# CONNECTOR.net
KiCad netlist of a schematic drawn in Altium Designer
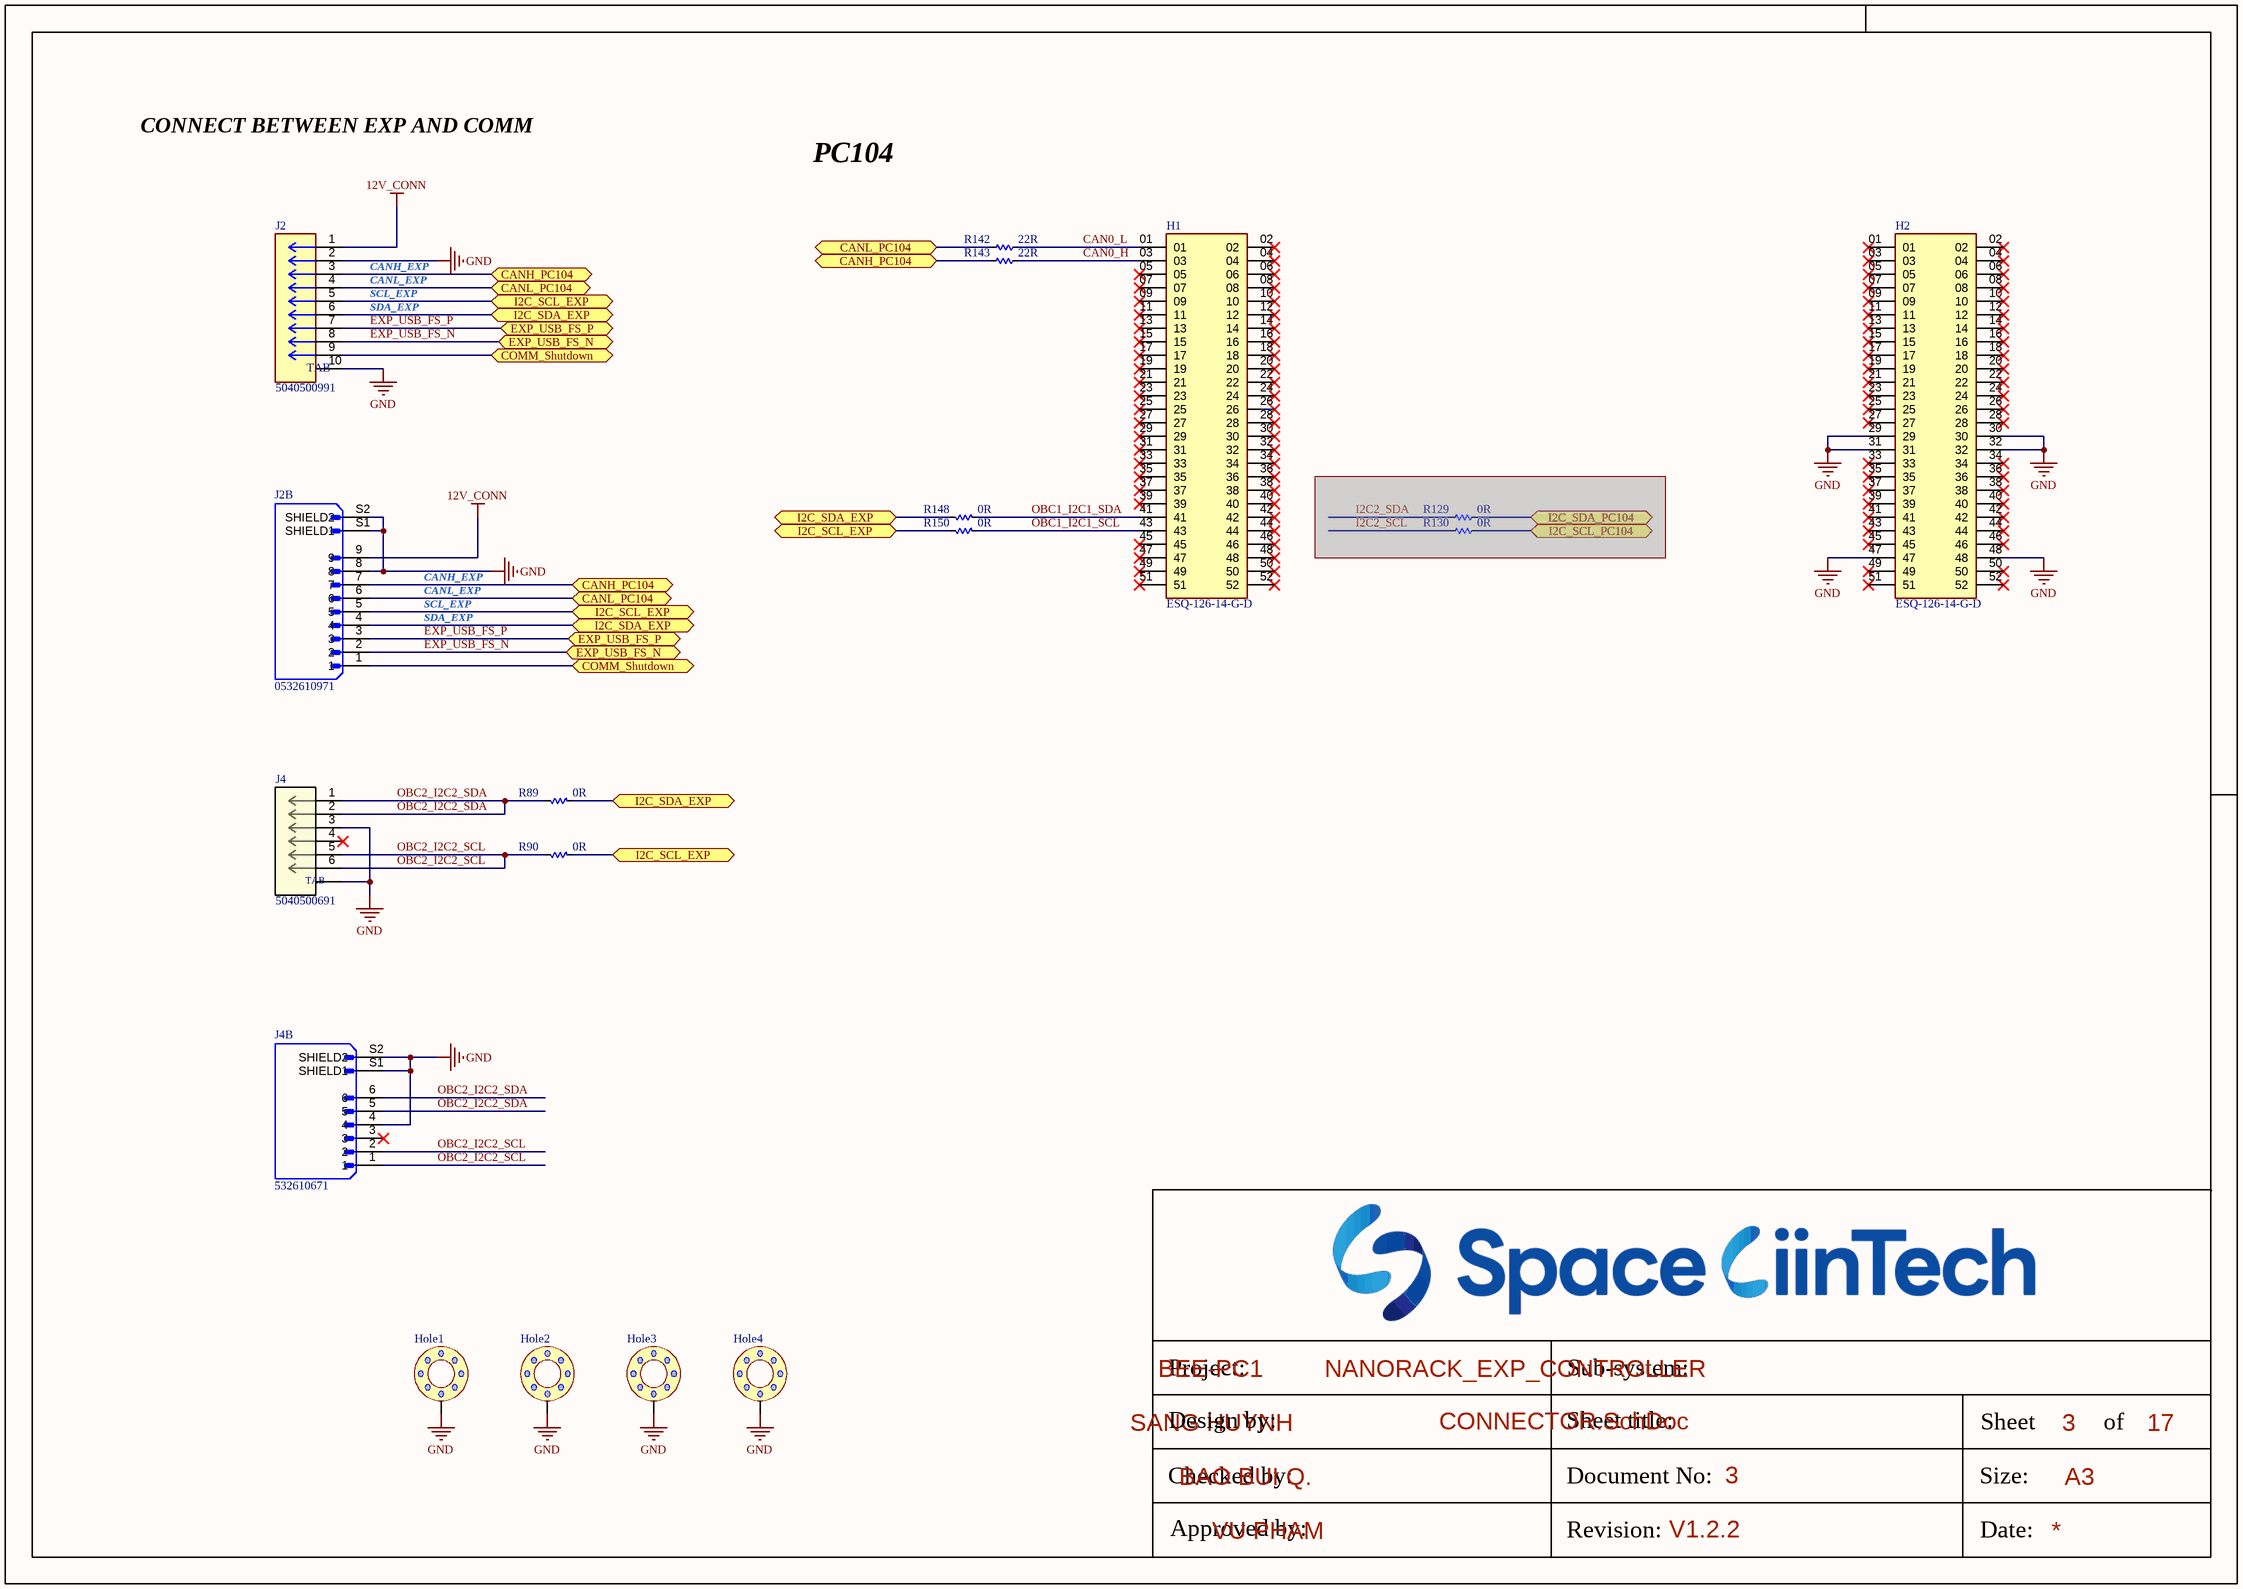
[diagram p0: CONNECTOR.SchDoc]

(export (version "E")
  (design (tool "Eeschema 10.0.6"))
  (components
    (comp (ref "H1")
      (value "ESQ-126-14-G-D")
      (footprint "SAMTEC_ESQ-126-14-G-D")
      (fields (field (name "MF") "Samtec"))
      (libsource (lib "COMM_SCHLIB") (part "ESQ-126-14-G-D"))
    )
    (comp (ref "H2")
      (value "ESQ-126-14-G-D")
      (footprint "SAMTEC_ESQ-126-14-G-D")
      (fields (field (name "MF") "Samtec"))
      (libsource (lib "COMM_SCHLIB") (part "ESQ-126-14-G-D"))
    )
    (comp (ref "Hole1")
      (value "hole_space")
      (footprint "HOLE_SPACE")
      (libsource (lib "COMM_SCHLIB") (part "hole_space"))
    )
    (comp (ref "Hole2")
      (value "hole_space")
      (footprint "HOLE_SPACE")
      (libsource (lib "COMM_SCHLIB") (part "hole_space"))
    )
    (comp (ref "Hole3")
      (value "hole_space")
      (footprint "HOLE_SPACE")
      (libsource (lib "COMM_SCHLIB") (part "hole_space"))
    )
    (comp (ref "Hole4")
      (value "hole_space")
      (footprint "HOLE_SPACE")
      (libsource (lib "COMM_SCHLIB") (part "hole_space"))
    )
    (comp (ref "J2")
      (value "5040500991")
      (footprint "5040500991")
      (description "Connector Header Surface Mount, Right Angle 9 position 0.059\" (1.50mm)")
      (libsource (lib "COMM_SCHLIB") (part "5040500991"))
    )
    (comp (ref "J2B")
      (value "0532610971")
      (footprint "0532610971")
      (description "CONN HEADER SMD R/A 9POS 1.25MM")
      (libsource (lib "COMM_SCHLIB") (part "CONN_SMD_09"))
    )
    (comp (ref "J4")
      (value "5040500691")
      (footprint "5040500691")
      (fields (field (name "COPYRIGHT") "Copyright (C) 2025 Ultra Librarian. All rights reserved."))
      (libsource (lib "COMM_SCHLIB") (part "5040500691"))
    )
    (comp (ref "J4B")
      (value "532610671")
      (footprint "MOLEX_532610671")
      (libsource (lib "COMM_SCHLIB") (part "CONN_SMD_06"))
    )
    (comp (ref "R89")
      (value "0R")
      (footprint "RES_C_1608X60")
      (description "RES")
      (libsource (lib "LABLIB") (part "_RES_B_2"))
    )
    (comp (ref "R90")
      (value "0R")
      (footprint "RES_C_1608X60")
      (description "RES")
      (libsource (lib "LABLIB") (part "_RES_B_2"))
    )
    (comp (ref "R129")
      (value "0R")
      (footprint "RES_C_1608X60")
      (description "RES")
      (libsource (lib "LABLIB") (part "_RES_B_2"))
    )
    (comp (ref "R130")
      (value "0R")
      (footprint "RES_C_1608X60")
      (description "RES")
      (libsource (lib "LABLIB") (part "_RES_B_2"))
    )
    (comp (ref "R142")
      (value "22R")
      (footprint "RES_C_1608X60")
      (description "RES")
      (libsource (lib "LABLIB") (part "_RES_B_2"))
    )
    (comp (ref "R143")
      (value "22R")
      (footprint "RES_C_1608X60")
      (description "RES")
      (libsource (lib "LABLIB") (part "_RES_B_2"))
    )
    (comp (ref "R148")
      (value "0R")
      (footprint "RES_C_1608X60")
      (description "RES")
      (libsource (lib "LABLIB") (part "_RES_B_2"))
    )
    (comp (ref "R150")
      (value "0R")
      (footprint "RES_C_1608X60")
      (description "RES")
      (libsource (lib "LABLIB") (part "_RES_B_2"))
    )
  )
  (nets
    (net (code "1") (name "/CAN0_H") (class "Default")
      (node (ref "H1") (pin "03") (pinfunction "03_03") (pintype "passive"))
      (node (ref "R143") (pin "2") (pinfunction "2_2") (pintype "passive"))
    )
    (net (code "2") (name "/CAN0_L") (class "Default")
      (node (ref "H1") (pin "01") (pinfunction "01_01") (pintype "passive"))
      (node (ref "R142") (pin "2") (pinfunction "2_2") (pintype "passive"))
    )
    (net (code "3") (name "/CANH_PC104") (class "Default")
      (node (ref "J2") (pin "3") (pinfunction "3_3") (pintype "passive"))
      (node (ref "J2B") (pin "7") (pinfunction "7_7") (pintype "passive"))
      (node (ref "R143") (pin "1") (pinfunction "1_1") (pintype "passive"))
    )
    (net (code "4") (name "/CANL_PC104") (class "Default")
      (node (ref "J2") (pin "4") (pinfunction "4_4") (pintype "passive"))
      (node (ref "J2B") (pin "6") (pinfunction "6_6") (pintype "passive"))
      (node (ref "R142") (pin "1") (pinfunction "1_1") (pintype "passive"))
    )
    (net (code "5") (name "/COMM_Shutdown") (class "Default")
      (node (ref "J2") (pin "9") (pinfunction "9_9") (pintype "passive"))
      (node (ref "J2B") (pin "1") (pinfunction "1_1") (pintype "passive"))
    )
    (net (code "6") (name "/EXP_USB_FS_N") (class "Default")
      (node (ref "J2") (pin "8") (pinfunction "8_8") (pintype "passive"))
      (node (ref "J2B") (pin "2") (pinfunction "2_2") (pintype "passive"))
    )
    (net (code "7") (name "/EXP_USB_FS_P") (class "Default")
      (node (ref "J2") (pin "7") (pinfunction "7_7") (pintype "passive"))
      (node (ref "J2B") (pin "3") (pinfunction "3_3") (pintype "passive"))
    )
    (net (code "8") (name "/I2C2_SCL") (class "Default")
      (node (ref "R130") (pin "1") (pinfunction "1_1") (pintype "passive"))
    )
    (net (code "9") (name "/I2C2_SDA") (class "Default")
      (node (ref "R129") (pin "1") (pinfunction "1_1") (pintype "passive"))
    )
    (net (code "10") (name "/I2C_SCL_EXP") (class "Default")
      (node (ref "J2") (pin "5") (pinfunction "5_5") (pintype "passive"))
      (node (ref "J2B") (pin "5") (pinfunction "5_5") (pintype "passive"))
      (node (ref "R150") (pin "2") (pinfunction "2_2") (pintype "passive"))
      (node (ref "R90") (pin "1") (pinfunction "1_1") (pintype "passive"))
    )
    (net (code "11") (name "/I2C_SCL_PC104") (class "Default")
      (node (ref "R130") (pin "2") (pinfunction "2_2") (pintype "passive"))
    )
    (net (code "12") (name "/I2C_SDA_EXP") (class "Default")
      (node (ref "J2") (pin "6") (pinfunction "6_6") (pintype "passive"))
      (node (ref "J2B") (pin "4") (pinfunction "4_4") (pintype "passive"))
      (node (ref "R148") (pin "2") (pinfunction "2_2") (pintype "passive"))
      (node (ref "R89") (pin "1") (pinfunction "1_1") (pintype "passive"))
    )
    (net (code "13") (name "/I2C_SDA_PC104") (class "Default")
      (node (ref "R129") (pin "2") (pinfunction "2_2") (pintype "passive"))
    )
    (net (code "14") (name "/OBC1_I2C1_SCL") (class "Default")
      (node (ref "H1") (pin "43") (pinfunction "43_43") (pintype "passive"))
      (node (ref "R150") (pin "1") (pinfunction "1_1") (pintype "passive"))
    )
    (net (code "15") (name "/OBC1_I2C1_SDA") (class "Default")
      (node (ref "H1") (pin "41") (pinfunction "41_41") (pintype "passive"))
      (node (ref "R148") (pin "1") (pinfunction "1_1") (pintype "passive"))
    )
    (net (code "16") (name "/OBC2_I2C2_SCL") (class "Default")
      (node (ref "J4") (pin "5") (pinfunction "5_5") (pintype "passive"))
      (node (ref "J4") (pin "6") (pinfunction "6_6") (pintype "passive"))
      (node (ref "J4B") (pin "1") (pinfunction "1_1") (pintype "passive"))
      (node (ref "J4B") (pin "2") (pinfunction "2_2") (pintype "passive"))
      (node (ref "R90") (pin "2") (pinfunction "2_2") (pintype "passive"))
    )
    (net (code "17") (name "/OBC2_I2C2_SDA") (class "Default")
      (node (ref "J4") (pin "1") (pinfunction "1_1") (pintype "passive"))
      (node (ref "J4") (pin "2") (pinfunction "2_2") (pintype "passive"))
      (node (ref "J4B") (pin "5") (pinfunction "5_5") (pintype "passive"))
      (node (ref "J4B") (pin "6") (pinfunction "6_6") (pintype "passive"))
      (node (ref "R89") (pin "2") (pinfunction "2_2") (pintype "passive"))
    )
    (net (code "18") (name "12V_CONN") (class "Default")
      (node (ref "J2") (pin "1") (pinfunction "1_1") (pintype "passive"))
      (node (ref "J2B") (pin "9") (pinfunction "9_9") (pintype "passive"))
    )
    (net (code "19") (name "GND") (class "Default")
      (node (ref "H2") (pin "29") (pinfunction "29_29") (pintype "passive"))
      (node (ref "H2") (pin "30") (pinfunction "30_30") (pintype "passive"))
      (node (ref "H2") (pin "31") (pinfunction "31_31") (pintype "passive"))
      (node (ref "H2") (pin "32") (pinfunction "32_32") (pintype "passive"))
      (node (ref "H2") (pin "47") (pinfunction "47_47") (pintype "passive"))
      (node (ref "H2") (pin "48") (pinfunction "48_48") (pintype "passive"))
      (node (ref "Hole1") (pin "1") (pinfunction "1_1") (pintype "passive"))
      (node (ref "Hole2") (pin "1") (pinfunction "1_1") (pintype "passive"))
      (node (ref "Hole3") (pin "1") (pinfunction "1_1") (pintype "passive"))
      (node (ref "Hole4") (pin "1") (pinfunction "1_1") (pintype "passive"))
      (node (ref "J2") (pin "10") (pinfunction "10_10") (pintype "passive"))
      (node (ref "J2") (pin "2") (pinfunction "2_2") (pintype "passive"))
      (node (ref "J2B") (pin "8") (pinfunction "8_8") (pintype "passive"))
      (node (ref "J2B") (pin "S1") (pinfunction "SHIELD1_S1") (pintype "passive"))
      (node (ref "J2B") (pin "S2") (pinfunction "SHIELD2_S2") (pintype "passive"))
      (node (ref "J4") (pin "3") (pinfunction "3_3") (pintype "passive"))
      (node (ref "J4") (pin "7") (pinfunction "7_7") (pintype "passive"))
      (node (ref "J4B") (pin "4") (pinfunction "4_4") (pintype "passive"))
      (node (ref "J4B") (pin "S1") (pinfunction "SHIELD1_S1") (pintype "passive"))
      (node (ref "J4B") (pin "S2") (pinfunction "SHIELD2_S2") (pintype "passive"))
    )
    (net (code "20") (name "unconnected-(H1-Pad02)") (class "Default")
      (node (ref "H1") (pin "02") (pinfunction "02_02") (pintype "passive+no_connect"))
    )
    (net (code "21") (name "unconnected-(H1-Pad04)") (class "Default")
      (node (ref "H1") (pin "04") (pinfunction "04_04") (pintype "passive+no_connect"))
    )
    (net (code "22") (name "unconnected-(H1-Pad05)") (class "Default")
      (node (ref "H1") (pin "05") (pinfunction "05_05") (pintype "passive+no_connect"))
    )
    (net (code "23") (name "unconnected-(H1-Pad06)") (class "Default")
      (node (ref "H1") (pin "06") (pinfunction "06_06") (pintype "passive+no_connect"))
    )
    (net (code "24") (name "unconnected-(H1-Pad07)") (class "Default")
      (node (ref "H1") (pin "07") (pinfunction "07_07") (pintype "passive+no_connect"))
    )
    (net (code "25") (name "unconnected-(H1-Pad08)") (class "Default")
      (node (ref "H1") (pin "08") (pinfunction "08_08") (pintype "passive+no_connect"))
    )
    (net (code "26") (name "unconnected-(H1-Pad09)") (class "Default")
      (node (ref "H1") (pin "09") (pinfunction "09_09") (pintype "passive+no_connect"))
    )
    (net (code "27") (name "unconnected-(H1-Pad10)") (class "Default")
      (node (ref "H1") (pin "10") (pinfunction "10_10") (pintype "passive+no_connect"))
    )
    (net (code "28") (name "unconnected-(H1-Pad11)") (class "Default")
      (node (ref "H1") (pin "11") (pinfunction "11_11") (pintype "passive+no_connect"))
    )
    (net (code "29") (name "unconnected-(H1-Pad12)") (class "Default")
      (node (ref "H1") (pin "12") (pinfunction "12_12") (pintype "passive+no_connect"))
    )
    (net (code "30") (name "unconnected-(H1-Pad13)") (class "Default")
      (node (ref "H1") (pin "13") (pinfunction "13_13") (pintype "passive+no_connect"))
    )
    (net (code "31") (name "unconnected-(H1-Pad14)") (class "Default")
      (node (ref "H1") (pin "14") (pinfunction "14_14") (pintype "passive+no_connect"))
    )
    (net (code "32") (name "unconnected-(H1-Pad15)") (class "Default")
      (node (ref "H1") (pin "15") (pinfunction "15_15") (pintype "passive+no_connect"))
    )
    (net (code "33") (name "unconnected-(H1-Pad16)") (class "Default")
      (node (ref "H1") (pin "16") (pinfunction "16_16") (pintype "passive+no_connect"))
    )
    (net (code "34") (name "unconnected-(H1-Pad17)") (class "Default")
      (node (ref "H1") (pin "17") (pinfunction "17_17") (pintype "passive+no_connect"))
    )
    (net (code "35") (name "unconnected-(H1-Pad18)") (class "Default")
      (node (ref "H1") (pin "18") (pinfunction "18_18") (pintype "passive+no_connect"))
    )
    (net (code "36") (name "unconnected-(H1-Pad19)") (class "Default")
      (node (ref "H1") (pin "19") (pinfunction "19_19") (pintype "passive+no_connect"))
    )
    (net (code "37") (name "unconnected-(H1-Pad20)") (class "Default")
      (node (ref "H1") (pin "20") (pinfunction "20_20") (pintype "passive+no_connect"))
    )
    (net (code "38") (name "unconnected-(H1-Pad21)") (class "Default")
      (node (ref "H1") (pin "21") (pinfunction "21_21") (pintype "passive+no_connect"))
    )
    (net (code "39") (name "unconnected-(H1-Pad22)") (class "Default")
      (node (ref "H1") (pin "22") (pinfunction "22_22") (pintype "passive+no_connect"))
    )
    (net (code "40") (name "unconnected-(H1-Pad23)") (class "Default")
      (node (ref "H1") (pin "23") (pinfunction "23_23") (pintype "passive+no_connect"))
    )
    (net (code "41") (name "unconnected-(H1-Pad24)") (class "Default")
      (node (ref "H1") (pin "24") (pinfunction "24_24") (pintype "passive+no_connect"))
    )
    (net (code "42") (name "unconnected-(H1-Pad25)") (class "Default")
      (node (ref "H1") (pin "25") (pinfunction "25_25") (pintype "passive+no_connect"))
    )
    (net (code "43") (name "unconnected-(H1-Pad26)") (class "Default")
      (node (ref "H1") (pin "26") (pinfunction "26_26") (pintype "passive+no_connect"))
    )
    (net (code "44") (name "unconnected-(H1-Pad27)") (class "Default")
      (node (ref "H1") (pin "27") (pinfunction "27_27") (pintype "passive+no_connect"))
    )
    (net (code "45") (name "unconnected-(H1-Pad28)") (class "Default")
      (node (ref "H1") (pin "28") (pinfunction "28_28") (pintype "passive+no_connect"))
    )
    (net (code "46") (name "unconnected-(H1-Pad29)") (class "Default")
      (node (ref "H1") (pin "29") (pinfunction "29_29") (pintype "passive+no_connect"))
    )
    (net (code "47") (name "unconnected-(H1-Pad30)") (class "Default")
      (node (ref "H1") (pin "30") (pinfunction "30_30") (pintype "passive+no_connect"))
    )
    (net (code "48") (name "unconnected-(H1-Pad31)") (class "Default")
      (node (ref "H1") (pin "31") (pinfunction "31_31") (pintype "passive+no_connect"))
    )
    (net (code "49") (name "unconnected-(H1-Pad32)") (class "Default")
      (node (ref "H1") (pin "32") (pinfunction "32_32") (pintype "passive+no_connect"))
    )
    (net (code "50") (name "unconnected-(H1-Pad33)") (class "Default")
      (node (ref "H1") (pin "33") (pinfunction "33_33") (pintype "passive+no_connect"))
    )
    (net (code "51") (name "unconnected-(H1-Pad34)") (class "Default")
      (node (ref "H1") (pin "34") (pinfunction "34_34") (pintype "passive+no_connect"))
    )
    (net (code "52") (name "unconnected-(H1-Pad35)") (class "Default")
      (node (ref "H1") (pin "35") (pinfunction "35_35") (pintype "passive+no_connect"))
    )
    (net (code "53") (name "unconnected-(H1-Pad36)") (class "Default")
      (node (ref "H1") (pin "36") (pinfunction "36_36") (pintype "passive+no_connect"))
    )
    (net (code "54") (name "unconnected-(H1-Pad37)") (class "Default")
      (node (ref "H1") (pin "37") (pinfunction "37_37") (pintype "passive+no_connect"))
    )
    (net (code "55") (name "unconnected-(H1-Pad38)") (class "Default")
      (node (ref "H1") (pin "38") (pinfunction "38_38") (pintype "passive+no_connect"))
    )
    (net (code "56") (name "unconnected-(H1-Pad39)") (class "Default")
      (node (ref "H1") (pin "39") (pinfunction "39_39") (pintype "passive+no_connect"))
    )
    (net (code "57") (name "unconnected-(H1-Pad40)") (class "Default")
      (node (ref "H1") (pin "40") (pinfunction "40_40") (pintype "passive+no_connect"))
    )
    (net (code "58") (name "unconnected-(H1-Pad42)") (class "Default")
      (node (ref "H1") (pin "42") (pinfunction "42_42") (pintype "passive+no_connect"))
    )
    (net (code "59") (name "unconnected-(H1-Pad44)") (class "Default")
      (node (ref "H1") (pin "44") (pinfunction "44_44") (pintype "passive+no_connect"))
    )
    (net (code "60") (name "unconnected-(H1-Pad45)") (class "Default")
      (node (ref "H1") (pin "45") (pinfunction "45_45") (pintype "passive+no_connect"))
    )
    (net (code "61") (name "unconnected-(H1-Pad46)") (class "Default")
      (node (ref "H1") (pin "46") (pinfunction "46_46") (pintype "passive+no_connect"))
    )
    (net (code "62") (name "unconnected-(H1-Pad47)") (class "Default")
      (node (ref "H1") (pin "47") (pinfunction "47_47") (pintype "passive+no_connect"))
    )
    (net (code "63") (name "unconnected-(H1-Pad48)") (class "Default")
      (node (ref "H1") (pin "48") (pinfunction "48_48") (pintype "passive+no_connect"))
    )
    (net (code "64") (name "unconnected-(H1-Pad49)") (class "Default")
      (node (ref "H1") (pin "49") (pinfunction "49_49") (pintype "passive+no_connect"))
    )
    (net (code "65") (name "unconnected-(H1-Pad50)") (class "Default")
      (node (ref "H1") (pin "50") (pinfunction "50_50") (pintype "passive+no_connect"))
    )
    (net (code "66") (name "unconnected-(H1-Pad51)") (class "Default")
      (node (ref "H1") (pin "51") (pinfunction "51_51") (pintype "passive+no_connect"))
    )
    (net (code "67") (name "unconnected-(H1-Pad52)") (class "Default")
      (node (ref "H1") (pin "52") (pinfunction "52_52") (pintype "passive+no_connect"))
    )
    (net (code "68") (name "unconnected-(H2-Pad01)") (class "Default")
      (node (ref "H2") (pin "01") (pinfunction "01_01") (pintype "passive+no_connect"))
    )
    (net (code "69") (name "unconnected-(H2-Pad02)") (class "Default")
      (node (ref "H2") (pin "02") (pinfunction "02_02") (pintype "passive+no_connect"))
    )
    (net (code "70") (name "unconnected-(H2-Pad03)") (class "Default")
      (node (ref "H2") (pin "03") (pinfunction "03_03") (pintype "passive+no_connect"))
    )
    (net (code "71") (name "unconnected-(H2-Pad04)") (class "Default")
      (node (ref "H2") (pin "04") (pinfunction "04_04") (pintype "passive+no_connect"))
    )
    (net (code "72") (name "unconnected-(H2-Pad05)") (class "Default")
      (node (ref "H2") (pin "05") (pinfunction "05_05") (pintype "passive+no_connect"))
    )
    (net (code "73") (name "unconnected-(H2-Pad06)") (class "Default")
      (node (ref "H2") (pin "06") (pinfunction "06_06") (pintype "passive+no_connect"))
    )
    (net (code "74") (name "unconnected-(H2-Pad07)") (class "Default")
      (node (ref "H2") (pin "07") (pinfunction "07_07") (pintype "passive+no_connect"))
    )
    (net (code "75") (name "unconnected-(H2-Pad08)") (class "Default")
      (node (ref "H2") (pin "08") (pinfunction "08_08") (pintype "passive+no_connect"))
    )
    (net (code "76") (name "unconnected-(H2-Pad09)") (class "Default")
      (node (ref "H2") (pin "09") (pinfunction "09_09") (pintype "passive+no_connect"))
    )
    (net (code "77") (name "unconnected-(H2-Pad10)") (class "Default")
      (node (ref "H2") (pin "10") (pinfunction "10_10") (pintype "passive+no_connect"))
    )
    (net (code "78") (name "unconnected-(H2-Pad11)") (class "Default")
      (node (ref "H2") (pin "11") (pinfunction "11_11") (pintype "passive+no_connect"))
    )
    (net (code "79") (name "unconnected-(H2-Pad12)") (class "Default")
      (node (ref "H2") (pin "12") (pinfunction "12_12") (pintype "passive+no_connect"))
    )
    (net (code "80") (name "unconnected-(H2-Pad13)") (class "Default")
      (node (ref "H2") (pin "13") (pinfunction "13_13") (pintype "passive+no_connect"))
    )
    (net (code "81") (name "unconnected-(H2-Pad14)") (class "Default")
      (node (ref "H2") (pin "14") (pinfunction "14_14") (pintype "passive+no_connect"))
    )
    (net (code "82") (name "unconnected-(H2-Pad15)") (class "Default")
      (node (ref "H2") (pin "15") (pinfunction "15_15") (pintype "passive+no_connect"))
    )
    (net (code "83") (name "unconnected-(H2-Pad16)") (class "Default")
      (node (ref "H2") (pin "16") (pinfunction "16_16") (pintype "passive+no_connect"))
    )
    (net (code "84") (name "unconnected-(H2-Pad17)") (class "Default")
      (node (ref "H2") (pin "17") (pinfunction "17_17") (pintype "passive+no_connect"))
    )
    (net (code "85") (name "unconnected-(H2-Pad18)") (class "Default")
      (node (ref "H2") (pin "18") (pinfunction "18_18") (pintype "passive+no_connect"))
    )
    (net (code "86") (name "unconnected-(H2-Pad19)") (class "Default")
      (node (ref "H2") (pin "19") (pinfunction "19_19") (pintype "passive+no_connect"))
    )
    (net (code "87") (name "unconnected-(H2-Pad20)") (class "Default")
      (node (ref "H2") (pin "20") (pinfunction "20_20") (pintype "passive+no_connect"))
    )
    (net (code "88") (name "unconnected-(H2-Pad21)") (class "Default")
      (node (ref "H2") (pin "21") (pinfunction "21_21") (pintype "passive+no_connect"))
    )
    (net (code "89") (name "unconnected-(H2-Pad22)") (class "Default")
      (node (ref "H2") (pin "22") (pinfunction "22_22") (pintype "passive+no_connect"))
    )
    (net (code "90") (name "unconnected-(H2-Pad23)") (class "Default")
      (node (ref "H2") (pin "23") (pinfunction "23_23") (pintype "passive+no_connect"))
    )
    (net (code "91") (name "unconnected-(H2-Pad24)") (class "Default")
      (node (ref "H2") (pin "24") (pinfunction "24_24") (pintype "passive+no_connect"))
    )
    (net (code "92") (name "unconnected-(H2-Pad25)") (class "Default")
      (node (ref "H2") (pin "25") (pinfunction "25_25") (pintype "passive+no_connect"))
    )
    (net (code "93") (name "unconnected-(H2-Pad26)") (class "Default")
      (node (ref "H2") (pin "26") (pinfunction "26_26") (pintype "passive+no_connect"))
    )
    (net (code "94") (name "unconnected-(H2-Pad27)") (class "Default")
      (node (ref "H2") (pin "27") (pinfunction "27_27") (pintype "passive+no_connect"))
    )
    (net (code "95") (name "unconnected-(H2-Pad28)") (class "Default")
      (node (ref "H2") (pin "28") (pinfunction "28_28") (pintype "passive+no_connect"))
    )
    (net (code "96") (name "unconnected-(H2-Pad33)") (class "Default")
      (node (ref "H2") (pin "33") (pinfunction "33_33") (pintype "passive+no_connect"))
    )
    (net (code "97") (name "unconnected-(H2-Pad34)") (class "Default")
      (node (ref "H2") (pin "34") (pinfunction "34_34") (pintype "passive+no_connect"))
    )
    (net (code "98") (name "unconnected-(H2-Pad35)") (class "Default")
      (node (ref "H2") (pin "35") (pinfunction "35_35") (pintype "passive+no_connect"))
    )
    (net (code "99") (name "unconnected-(H2-Pad36)") (class "Default")
      (node (ref "H2") (pin "36") (pinfunction "36_36") (pintype "passive+no_connect"))
    )
    (net (code "100") (name "unconnected-(H2-Pad37)") (class "Default")
      (node (ref "H2") (pin "37") (pinfunction "37_37") (pintype "passive+no_connect"))
    )
    (net (code "101") (name "unconnected-(H2-Pad38)") (class "Default")
      (node (ref "H2") (pin "38") (pinfunction "38_38") (pintype "passive+no_connect"))
    )
    (net (code "102") (name "unconnected-(H2-Pad39)") (class "Default")
      (node (ref "H2") (pin "39") (pinfunction "39_39") (pintype "passive+no_connect"))
    )
    (net (code "103") (name "unconnected-(H2-Pad40)") (class "Default")
      (node (ref "H2") (pin "40") (pinfunction "40_40") (pintype "passive+no_connect"))
    )
    (net (code "104") (name "unconnected-(H2-Pad41)") (class "Default")
      (node (ref "H2") (pin "41") (pinfunction "41_41") (pintype "passive+no_connect"))
    )
    (net (code "105") (name "unconnected-(H2-Pad42)") (class "Default")
      (node (ref "H2") (pin "42") (pinfunction "42_42") (pintype "passive+no_connect"))
    )
    (net (code "106") (name "unconnected-(H2-Pad43)") (class "Default")
      (node (ref "H2") (pin "43") (pinfunction "43_43") (pintype "passive+no_connect"))
    )
    (net (code "107") (name "unconnected-(H2-Pad44)") (class "Default")
      (node (ref "H2") (pin "44") (pinfunction "44_44") (pintype "passive+no_connect"))
    )
    (net (code "108") (name "unconnected-(H2-Pad45)") (class "Default")
      (node (ref "H2") (pin "45") (pinfunction "45_45") (pintype "passive+no_connect"))
    )
    (net (code "109") (name "unconnected-(H2-Pad46)") (class "Default")
      (node (ref "H2") (pin "46") (pinfunction "46_46") (pintype "passive+no_connect"))
    )
    (net (code "110") (name "unconnected-(H2-Pad49)") (class "Default")
      (node (ref "H2") (pin "49") (pinfunction "49_49") (pintype "passive+no_connect"))
    )
    (net (code "111") (name "unconnected-(H2-Pad50)") (class "Default")
      (node (ref "H2") (pin "50") (pinfunction "50_50") (pintype "passive+no_connect"))
    )
    (net (code "112") (name "unconnected-(H2-Pad51)") (class "Default")
      (node (ref "H2") (pin "51") (pinfunction "51_51") (pintype "passive+no_connect"))
    )
    (net (code "113") (name "unconnected-(H2-Pad52)") (class "Default")
      (node (ref "H2") (pin "52") (pinfunction "52_52") (pintype "passive+no_connect"))
    )
    (net (code "114") (name "unconnected-(J4-Pad4)") (class "Default")
      (node (ref "J4") (pin "4") (pinfunction "4_4") (pintype "passive+no_connect"))
    )
    (net (code "115") (name "unconnected-(J4B-Pad3)") (class "Default")
      (node (ref "J4B") (pin "3") (pinfunction "3_3") (pintype "passive+no_connect"))
    )
  )
)
